# Outputs.net
KiCad netlist of a schematic drawn in Altium Designer
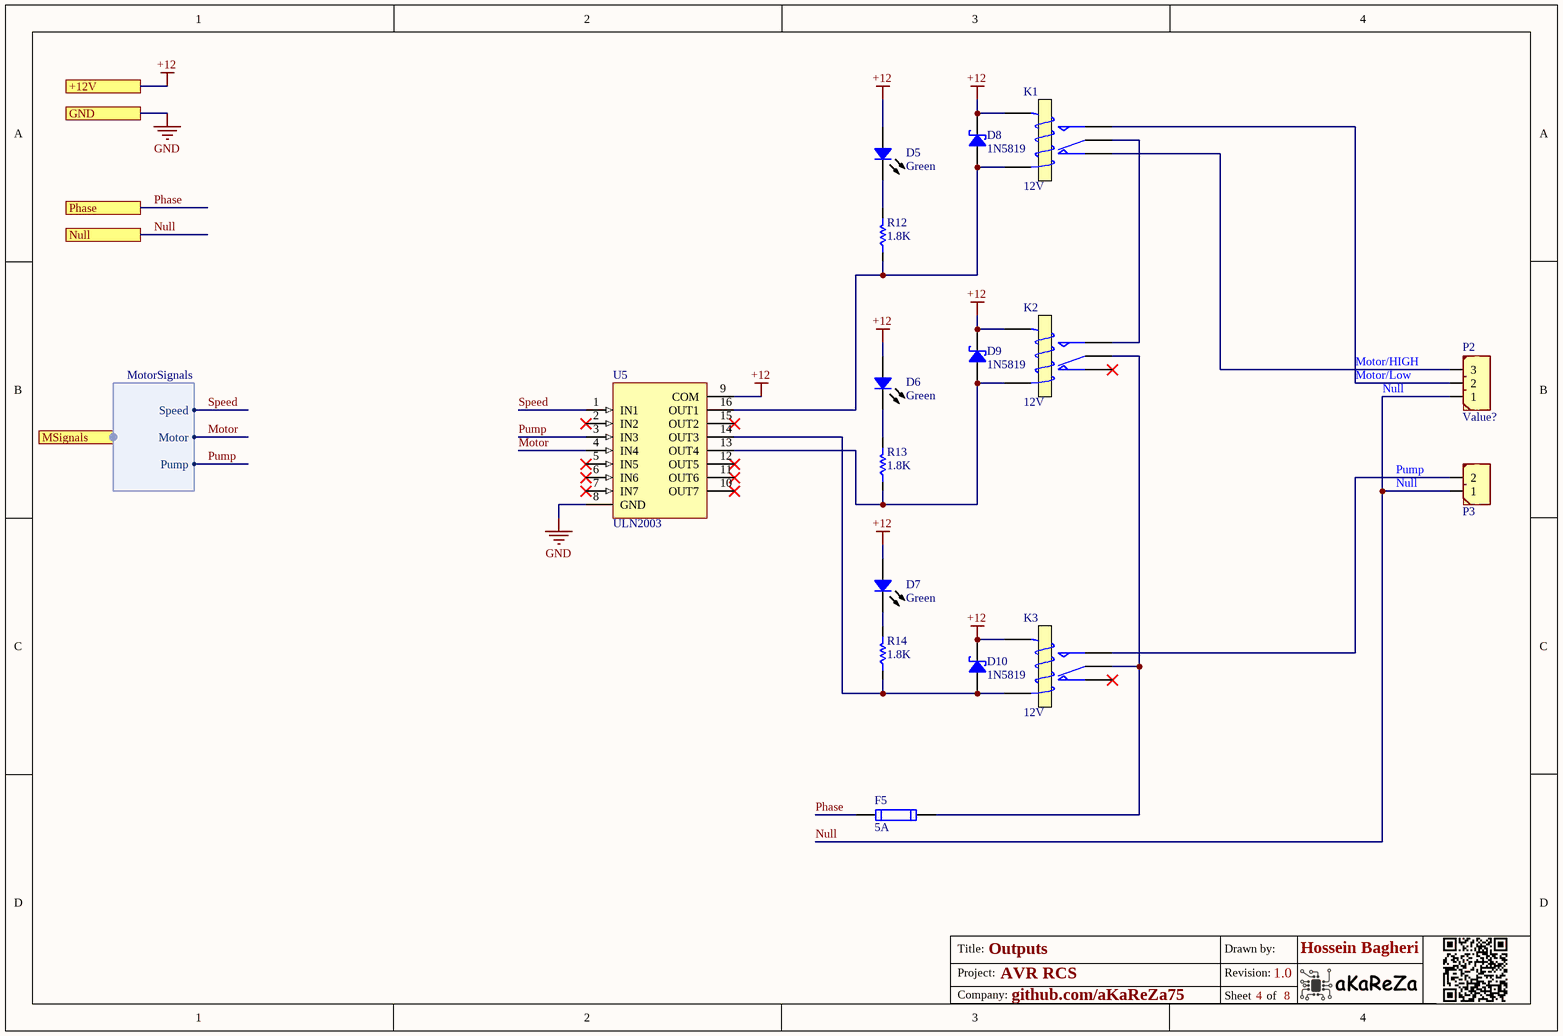
[diagram p0: Outputs.SchDoc]

(export (version "E")
  (design (tool "Eeschema 10.0.6"))
  (components
    (comp (ref "D5")
      (value "Green")
      (footprint "LED 0805/2012 GREEN")
      (description "LED")
      (fields (field (name "VALIDATION") "Valid"))
      (libsource (lib "aKaReZa") (part "Semi_LED_SMD"))
    )
    (comp (ref "D6")
      (value "Green")
      (footprint "LED 0805/2012 GREEN")
      (description "LED")
      (fields (field (name "VALIDATION") "Valid"))
      (libsource (lib "aKaReZa") (part "Semi_LED_SMD"))
    )
    (comp (ref "D7")
      (value "Green")
      (footprint "LED 0805/2012 GREEN")
      (description "LED")
      (fields (field (name "VALIDATION") "Valid"))
      (libsource (lib "aKaReZa") (part "Semi_LED_SMD"))
    )
    (comp (ref "D8")
      (value "1N5819")
      (footprint "430X270D")
      (description "Schottky Rectifiers")
      (fields (field (name "VALIDATION") "Valid"))
      (libsource (lib "aKaReZa") (part "Semi_Diod_Sch_1N5819_SMD"))
    )
    (comp (ref "D9")
      (value "1N5819")
      (footprint "430X270D")
      (description "Schottky Rectifiers")
      (fields (field (name "VALIDATION") "Valid"))
      (libsource (lib "aKaReZa") (part "Semi_Diod_Sch_1N5819_SMD"))
    )
    (comp (ref "D10")
      (value "1N5819")
      (footprint "430X270D")
      (description "Schottky Rectifiers")
      (fields (field (name "VALIDATION") "Valid"))
      (libsource (lib "aKaReZa") (part "Semi_Diod_Sch_1N5819_SMD"))
    )
    (comp (ref "F5")
      (value "5A")
      (footprint "FUSE_BLX_20x5")
      (description "Short circiut  protection")
      (fields (field (name "VALIDATION") "Valid"))
      (libsource (lib "aKaReZa") (part "Other_Elec_Fuse_THT"))
    )
    (comp (ref "K1")
      (value "12V")
      (footprint "Relay 18.85x15.35x15.70")
      (description "SPDT Relay")
      (fields (field (name "VALIDATION") "Valid"))
      (libsource (lib "aKaReZa") (part "SW_Relay_SPDT"))
    )
    (comp (ref "K2")
      (value "12V")
      (footprint "Relay 18.85x15.35x15.70")
      (description "SPDT Relay")
      (fields (field (name "VALIDATION") "Valid"))
      (libsource (lib "aKaReZa") (part "SW_Relay_SPDT"))
    )
    (comp (ref "K3")
      (value "12V")
      (footprint "Relay 18.85x15.35x15.70")
      (description "SPDT Relay")
      (fields (field (name "VALIDATION") "Valid"))
      (libsource (lib "aKaReZa") (part "SW_Relay_SPDT"))
    )
    (comp (ref "P2")
      (value "Value?")
      (footprint "Phoenix_3PIN_RA_P5.08mm")
      (description "Power Connector 3'Pin")
      (fields (field (name "VALIDATION") "Valid"))
      (libsource (lib "aKaReZa") (part "Con_Power_3"))
    )
    (comp (ref "P3")
      (value "2'Pin")
      (footprint "Phoenix_2PIN_RA_P5.08mm")
      (description "Power Connector 2'Pin")
      (fields (field (name "VALIDATION") "NT"))
      (libsource (lib "aKaReZa") (part "Con_Power_2"))
    )
    (comp (ref "R12")
      (value "1.8K")
      (footprint "RES 0805 (2012X06L)")
      (description "Resistor")
      (fields (field (name "VALIDATION") "Valid"))
      (libsource (lib "aKaReZa") (part "Res_SMD_0805"))
    )
    (comp (ref "R13")
      (value "1.8K")
      (footprint "RES 0805 (2012X06L)")
      (description "Resistor")
      (fields (field (name "VALIDATION") "Valid"))
      (libsource (lib "aKaReZa") (part "Res_SMD_0805"))
    )
    (comp (ref "R14")
      (value "1.8K")
      (footprint "RES 0805 (2012X06L)")
      (description "Resistor")
      (fields (field (name "VALIDATION") "Valid"))
      (libsource (lib "aKaReZa") (part "Res_SMD_0805"))
    )
    (comp (ref "U5")
      (value "ULN2003")
      (footprint "SO16_M")
      (description "Seven darlington array drivers")
      (fields (field (name "VALIDATION") "Valid"))
      (libsource (lib "aKaReZa") (part "IC_Driver_ULN2003"))
    )
  )
  (nets
    (net (code "2") (name "+12") (class "Default")
      (node (ref "D10") (pin "2") (pinfunction "2_2") (pintype "passive"))
      (node (ref "D5") (pin "1") (pinfunction "1_1") (pintype "passive"))
      (node (ref "D6") (pin "1") (pinfunction "1_1") (pintype "passive"))
      (node (ref "D7") (pin "1") (pinfunction "1_1") (pintype "passive"))
      (node (ref "D8") (pin "2") (pinfunction "2_2") (pintype "passive"))
      (node (ref "D9") (pin "2") (pinfunction "2_2") (pintype "passive"))
      (node (ref "K1") (pin "5") (pinfunction "T2_5") (pintype "passive"))
      (node (ref "K2") (pin "5") (pinfunction "T2_5") (pintype "passive"))
      (node (ref "K3") (pin "5") (pinfunction "T2_5") (pintype "passive"))
      (node (ref "U5") (pin "9") (pinfunction "COM_9") (pintype "passive"))
    )
    (net (code "3") (name "/Motor") (class "Default")
      (node (ref "U5") (pin "4") (pinfunction "IN4_4") (pintype "input"))
    )
    (net (code "4") (name "/Null") (class "Default")
      (node (ref "P2") (pin "1") (pinfunction "1_1") (pintype "passive"))
      (node (ref "P3") (pin "1") (pinfunction "1_1") (pintype "passive"))
    )
    (net (code "5") (name "/Phase") (class "Default")
      (node (ref "F5") (pin "1") (pinfunction "1_1") (pintype "passive"))
    )
    (net (code "6") (name "/Pump") (class "Default")
      (node (ref "U5") (pin "3") (pinfunction "IN3_3") (pintype "input"))
    )
    (net (code "7") (name "/Speed") (class "Default")
      (node (ref "U5") (pin "1") (pinfunction "IN1_1") (pintype "input"))
    )
    (net (code "9") (name "GND") (class "Default")
      (node (ref "U5") (pin "8") (pinfunction "GND_8") (pintype "power_in"))
    )
    (net (code "10") (name "Net-(D5-Pad2)") (class "Default")
      (node (ref "D5") (pin "2") (pinfunction "2_2") (pintype "passive"))
      (node (ref "R12") (pin "2") (pinfunction "2_2") (pintype "passive"))
    )
    (net (code "11") (name "Net-(D6-Pad2)") (class "Default")
      (node (ref "D6") (pin "2") (pinfunction "2_2") (pintype "passive"))
      (node (ref "R13") (pin "2") (pinfunction "2_2") (pintype "passive"))
    )
    (net (code "12") (name "Net-(D7-Pad2)") (class "Default")
      (node (ref "D7") (pin "2") (pinfunction "2_2") (pintype "passive"))
      (node (ref "R14") (pin "2") (pinfunction "2_2") (pintype "passive"))
    )
    (net (code "13") (name "Net-(K1-COM)") (class "Default")
      (node (ref "K1") (pin "1") (pinfunction "COM_1") (pintype "passive"))
      (node (ref "K2") (pin "3") (pinfunction "NO_3") (pintype "passive"))
    )
    (net (code "14") (name "Net-(K1-NC)") (class "Default")
      (node (ref "K1") (pin "2") (pinfunction "NC_2") (pintype "passive"))
      (node (ref "P2") (pin "3") (pinfunction "3_3") (pintype "passive"))
    )
    (net (code "15") (name "Net-(K1-NO)") (class "Default")
      (node (ref "K1") (pin "3") (pinfunction "NO_3") (pintype "passive"))
      (node (ref "P2") (pin "2") (pinfunction "2_2") (pintype "passive"))
    )
    (net (code "16") (name "Net-(K1-T1)") (class "Default")
      (node (ref "D8") (pin "1") (pinfunction "1_1") (pintype "passive"))
      (node (ref "K1") (pin "4") (pinfunction "T1_4") (pintype "passive"))
      (node (ref "R12") (pin "1") (pinfunction "1_1") (pintype "passive"))
      (node (ref "U5") (pin "16") (pinfunction "OUT1_16") (pintype "open_collector"))
    )
    (net (code "17") (name "Net-(K2-COM)") (class "Default")
      (node (ref "F5") (pin "2") (pinfunction "2_2") (pintype "passive"))
      (node (ref "K2") (pin "1") (pinfunction "COM_1") (pintype "passive"))
      (node (ref "K3") (pin "1") (pinfunction "COM_1") (pintype "passive"))
    )
    (net (code "18") (name "Net-(K2-T1)") (class "Default")
      (node (ref "D9") (pin "1") (pinfunction "1_1") (pintype "passive"))
      (node (ref "K2") (pin "4") (pinfunction "T1_4") (pintype "passive"))
      (node (ref "R13") (pin "1") (pinfunction "1_1") (pintype "passive"))
      (node (ref "U5") (pin "13") (pinfunction "OUT4_13") (pintype "open_collector"))
    )
    (net (code "19") (name "Net-(K3-NO)") (class "Default")
      (node (ref "K3") (pin "3") (pinfunction "NO_3") (pintype "passive"))
      (node (ref "P3") (pin "2") (pinfunction "2_2") (pintype "passive"))
    )
    (net (code "20") (name "Net-(K3-T1)") (class "Default")
      (node (ref "D10") (pin "1") (pinfunction "1_1") (pintype "passive"))
      (node (ref "K3") (pin "4") (pinfunction "T1_4") (pintype "passive"))
      (node (ref "R14") (pin "1") (pinfunction "1_1") (pintype "passive"))
      (node (ref "U5") (pin "14") (pinfunction "OUT3_14") (pintype "open_collector"))
    )
    (net (code "21") (name "unconnected-(K2-NC-Pad2)") (class "Default")
      (node (ref "K2") (pin "2") (pinfunction "NC_2") (pintype "passive+no_connect"))
    )
    (net (code "22") (name "unconnected-(K3-NC-Pad2)") (class "Default")
      (node (ref "K3") (pin "2") (pinfunction "NC_2") (pintype "passive+no_connect"))
    )
    (net (code "23") (name "unconnected-(U5-IN2-Pad2)") (class "Default")
      (node (ref "U5") (pin "2") (pinfunction "IN2_2") (pintype "input+no_connect"))
    )
    (net (code "24") (name "unconnected-(U5-IN5-Pad5)") (class "Default")
      (node (ref "U5") (pin "5") (pinfunction "IN5_5") (pintype "input+no_connect"))
    )
    (net (code "25") (name "unconnected-(U5-IN6-Pad6)") (class "Default")
      (node (ref "U5") (pin "6") (pinfunction "IN6_6") (pintype "input+no_connect"))
    )
    (net (code "26") (name "unconnected-(U5-IN7-Pad7)") (class "Default")
      (node (ref "U5") (pin "7") (pinfunction "IN7_7") (pintype "input+no_connect"))
    )
    (net (code "27") (name "unconnected-(U5-OUT2-Pad15)") (class "Default")
      (node (ref "U5") (pin "15") (pinfunction "OUT2_15") (pintype "open_collector+no_connect"))
    )
    (net (code "28") (name "unconnected-(U5-OUT5-Pad12)") (class "Default")
      (node (ref "U5") (pin "12") (pinfunction "OUT5_12") (pintype "open_collector+no_connect"))
    )
    (net (code "29") (name "unconnected-(U5-OUT6-Pad11)") (class "Default")
      (node (ref "U5") (pin "11") (pinfunction "OUT6_11") (pintype "open_collector+no_connect"))
    )
    (net (code "30") (name "unconnected-(U5-OUT7-Pad10)") (class "Default")
      (node (ref "U5") (pin "10") (pinfunction "OUT7_10") (pintype "open_collector+no_connect"))
    )
  )
)
